# WIFI.net
KiCad netlist of a schematic drawn in Altium Designer
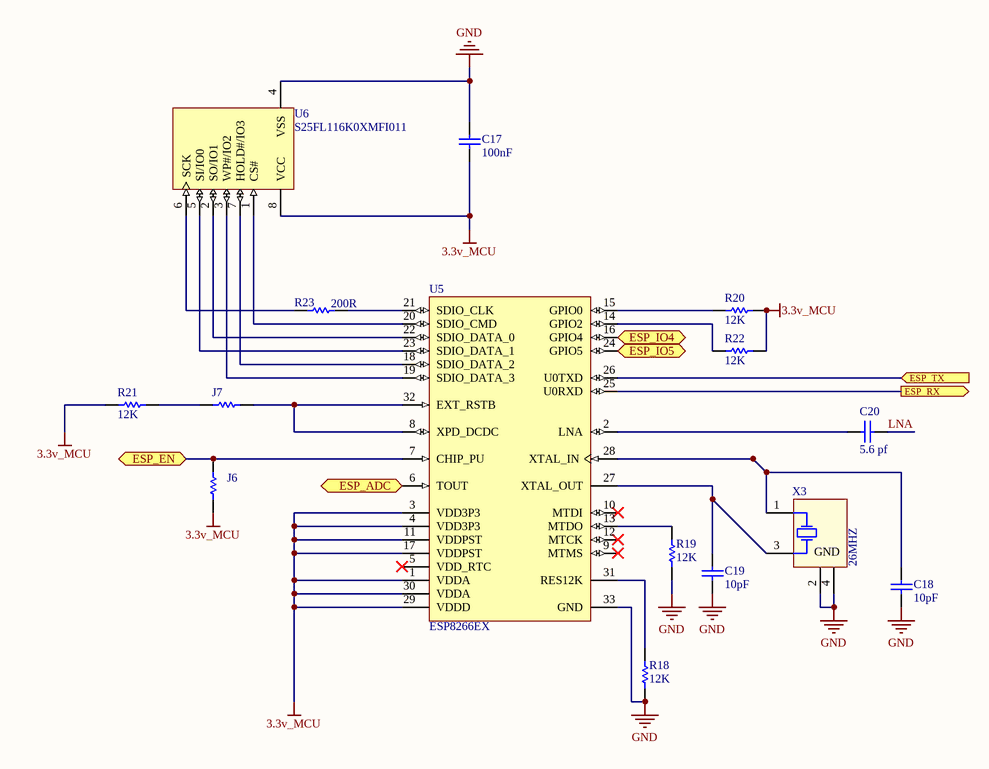
[diagram p0: WIFI.SchDoc]

(export (version "E")
  (design (tool "Eeschema 10.0.6"))
  (components
    (comp (ref "C17")
      (value "100nF")
      (footprint "CAPC0603(1608)100_L")
      (description "CAP 100nF 16V ±5% 0603 (1608 Metric) Thickness 1mm SMD")
      (fields (field (name "TOLERANCE") "Â±5%"))
      (libsource (lib "Altium Content Vault") (part "CAP"))
    )
    (comp (ref "C18")
      (value "10pF")
      (footprint "CAPC0603(1608)100_L")
      (description "CAP 10pF 16V ±1% 0603 (1608 Metric) Thickness 1mm SMD")
      (fields (field (name "TOLERANCE") "Â±1%"))
      (libsource (lib "Altium Content Vault") (part "CAP"))
    )
    (comp (ref "C19")
      (value "10pF")
      (footprint "CAPC0603(1608)100_L")
      (description "CAP 10pF 16V ±1% 0603 (1608 Metric) Thickness 1mm SMD")
      (fields (field (name "TOLERANCE") "Â±1%"))
      (libsource (lib "Altium Content Vault") (part "CAP"))
    )
    (comp (ref "C20")
      (value "5.6 pf")
      (footprint "CAPC0603(1608)100_L")
      (description "CAP 5.6pF 25V ±0.1pF 0603 (1608 Metric) Thickness 1mm SMD")
      (fields (field (name "TOLERANCE") "Â±0.1pF"))
      (libsource (lib "Altium Content Vault") (part "CAP"))
    )
    (comp (ref "J6")
      (value "~")
      (footprint "RESC1608X55X30LL10T20_A")
      (description "Chip Resistor, 0 Ohm, +/- 5%, 100 mW, -55 to 155 degC, 0603 (1608 Metric), RoHS, Tape and Reel")
      (fields (field (name "TOLERANCE") "Jumper") (field (name "MANUFACTURER") "Rohm"))
      (libsource (lib "Altium Content Vault") (part "RES-2"))
    )
    (comp (ref "J7")
      (value "~")
      (footprint "RESC1608X55X30LL10T20_A")
      (description "Chip Resistor, 0 Ohm, +/- 5%, 100 mW, -55 to 155 degC, 0603 (1608 Metric), RoHS, Tape and Reel")
      (fields (field (name "TOLERANCE") "Jumper") (field (name "MANUFACTURER") "Rohm"))
      (libsource (lib "Altium Content Vault") (part "RES-2"))
    )
    (comp (ref "R18")
      (value "12K")
      (footprint "RESC1609X55X30LL15T15")
      (description "Chip Resistor, 12 KOhm, +/- 1%, 0.1 W, -55 to 155 degC, 0603 (1608 Metric), RoHS, Tape and Reel")
      (fields (field (name "MANUFACTURER") "Panasonic") (field (name "TOLERANCE") "1%"))
      (libsource (lib "Altium Content Vault") (part "RES-2"))
    )
    (comp (ref "R19")
      (value "12K")
      (footprint "RESC1609X55X30LL15T15")
      (description "Chip Resistor, 12 KOhm, +/- 1%, 0.1 W, -55 to 155 degC, 0603 (1608 Metric), RoHS, Tape and Reel")
      (fields (field (name "MANUFACTURER") "Panasonic") (field (name "TOLERANCE") "1%"))
      (libsource (lib "Altium Content Vault") (part "RES-2"))
    )
    (comp (ref "R20")
      (value "12K")
      (footprint "RESC1609X55X30LL15T15")
      (description "Chip Resistor, 12 KOhm, +/- 1%, 0.1 W, -55 to 155 degC, 0603 (1608 Metric), RoHS, Tape and Reel")
      (fields (field (name "MANUFACTURER") "Panasonic") (field (name "TOLERANCE") "1%"))
      (libsource (lib "Altium Content Vault") (part "RES-2"))
    )
    (comp (ref "R21")
      (value "12K")
      (footprint "RESC1609X55X30LL15T15")
      (description "Chip Resistor, 12 KOhm, +/- 1%, 0.1 W, -55 to 155 degC, 0603 (1608 Metric), RoHS, Tape and Reel")
      (fields (field (name "MANUFACTURER") "Panasonic") (field (name "TOLERANCE") "1%"))
      (libsource (lib "Altium Content Vault") (part "RES-2"))
    )
    (comp (ref "R22")
      (value "12K")
      (footprint "RESC1609X55X30LL15T15")
      (description "Chip Resistor, 12 KOhm, +/- 1%, 0.1 W, -55 to 155 degC, 0603 (1608 Metric), RoHS, Tape and Reel")
      (fields (field (name "MANUFACTURER") "Panasonic") (field (name "TOLERANCE") "1%"))
      (libsource (lib "Altium Content Vault") (part "RES-2"))
    )
    (comp (ref "R23")
      (value "200R")
      (footprint "RESC0603(1608)_L")
      (description "200R 0.1W 1% 0603 (1608 Metric)  SMD")
      (fields (field (name "TOLERANCE") "1 %") (field (name "POWER") "0.1 W"))
      (libsource (lib "Altium Content Vault") (part "RES"))
    )
    (comp (ref "U5")
      (value "ESP8266EX")
      (footprint "ESFS-QFN-32_M")
      (description "Low-Power, Highly-Integrated Wi-Fi Solution, 2.5 to 3.6 V, 80 mA, -40 to 125 degC, 32-Pin QFN")
      (fields (field (name "MANUFACTURER") "Espressif Systems"))
      (libsource (lib "Altium Content Vault") (part "ESFS-ESP8266EX-32"))
    )
    (comp (ref "U6")
      (value "S25FL116K0XMFI011")
      (footprint "CYP-SOC-8_L")
      (description "SPI Flash Memory, 16 Mbit, 2.7 to 3.6 V, -40 to 85 degC, 8-Pin SOIC, RoHS, Tube")
      (fields (field (name "MANUFACTURER") "CypressSemiconductorCorp"))
      (libsource (lib "Altium Content Vault") (part "CYP-S25FL116K-SOIC-8"))
    )
    (comp (ref "X3")
      (value "26MHZ")
      (footprint "NDK-NX2016SA-26MHZ-EXS00A-CS06025-4_V")
      (description "Crystal, 26 MHz, 8 pF, for OA / AV / Short-range Wireless, -10 to 75 degC, 2.0 x 1.6 x 0.45 mm SMD")
      (fields (field (name "PARTNUMBER") "NX2016SA-26MHZ-EXS00A-CS06025") (field (name "MANUFACTURER") "NDK"))
      (libsource (lib "Altium Content Vault") (part "NDK-NX2016SA-26MHZ-EXS00A-CS06025-4"))
    )
  )
  (nets
    (net (code "1") (name "/ESP_ADC") (class "Default")
      (node (ref "U5") (pin "6") (pinfunction "TOUT_6") (pintype "input"))
    )
    (net (code "2") (name "/ESP_EN") (class "Default")
      (node (ref "J6") (pin "2") (pinfunction "2_2") (pintype "passive"))
      (node (ref "U5") (pin "7") (pinfunction "CHIP_PU_7") (pintype "input"))
    )
    (net (code "3") (name "/ESP_IO4") (class "Default")
      (node (ref "U5") (pin "16") (pinfunction "GPIO4_16") (pintype "bidirectional"))
    )
    (net (code "4") (name "/ESP_IO5") (class "Default")
      (node (ref "U5") (pin "24") (pinfunction "GPIO5_24") (pintype "bidirectional"))
    )
    (net (code "5") (name "/ESP_RX") (class "Default")
      (node (ref "U5") (pin "25") (pinfunction "U0RXD_25") (pintype "bidirectional"))
    )
    (net (code "6") (name "/ESP_TX") (class "Default")
      (node (ref "U5") (pin "26") (pinfunction "U0TXD_26") (pintype "bidirectional"))
    )
    (net (code "7") (name "/LNA") (class "Default")
      (node (ref "C20") (pin "2") (pinfunction "2_2") (pintype "passive"))
    )
    (net (code "8") (name "3.3v_MCU") (class "Default")
      (node (ref "C17") (pin "2") (pinfunction "2_2") (pintype "passive"))
      (node (ref "J6") (pin "1") (pinfunction "1_1") (pintype "passive"))
      (node (ref "R20") (pin "1") (pinfunction "1_1") (pintype "passive"))
      (node (ref "R21") (pin "2") (pinfunction "2_2") (pintype "passive"))
      (node (ref "R22") (pin "1") (pinfunction "1_1") (pintype "passive"))
      (node (ref "U5") (pin "1") (pinfunction "VDDA_1") (pintype "power_in"))
      (node (ref "U5") (pin "11") (pinfunction "VDDPST_11") (pintype "power_in"))
      (node (ref "U5") (pin "17") (pinfunction "VDDPST_17") (pintype "power_in"))
      (node (ref "U5") (pin "29") (pinfunction "VDDD_29") (pintype "power_in"))
      (node (ref "U5") (pin "3") (pinfunction "VDD3P3_3") (pintype "power_in"))
      (node (ref "U5") (pin "30") (pinfunction "VDDA_30") (pintype "power_in"))
      (node (ref "U5") (pin "4") (pinfunction "VDD3P3_4") (pintype "power_in"))
      (node (ref "U6") (pin "8") (pinfunction "VCC_8") (pintype "power_in"))
    )
    (net (code "9") (name "GND") (class "Default")
      (node (ref "C17") (pin "1") (pinfunction "1_1") (pintype "passive"))
      (node (ref "C18") (pin "1") (pinfunction "1_1") (pintype "passive"))
      (node (ref "C19") (pin "1") (pinfunction "1_1") (pintype "passive"))
      (node (ref "R18") (pin "1") (pinfunction "1_1") (pintype "passive"))
      (node (ref "R19") (pin "1") (pinfunction "1_1") (pintype "passive"))
      (node (ref "U5") (pin "33") (pinfunction "GND_33") (pintype "power_in"))
      (node (ref "U6") (pin "4") (pinfunction "VSS_4") (pintype "power_in"))
      (node (ref "X3") (pin "2") (pinfunction "GND_2") (pintype "power_in"))
      (node (ref "X3") (pin "4") (pinfunction "GND_4") (pintype "power_in"))
    )
    (net (code "10") (name "Net-(J7-Pad2)") (class "Default")
      (node (ref "J7") (pin "2") (pinfunction "2_2") (pintype "passive"))
      (node (ref "R21") (pin "1") (pinfunction "1_1") (pintype "passive"))
    )
    (net (code "11") (name "Net-(U5-EXT_RSTB)") (class "Default")
      (node (ref "J7") (pin "1") (pinfunction "1_1") (pintype "passive"))
      (node (ref "U5") (pin "32") (pinfunction "EXT_RSTB_32") (pintype "input"))
      (node (ref "U5") (pin "8") (pinfunction "XPD_DCDC_8") (pintype "bidirectional"))
    )
    (net (code "12") (name "Net-(U5-GPIO0)") (class "Default")
      (node (ref "R20") (pin "2") (pinfunction "2_2") (pintype "passive"))
      (node (ref "U5") (pin "15") (pinfunction "GPIO0_15") (pintype "bidirectional"))
    )
    (net (code "13") (name "Net-(U5-GPIO2)") (class "Default")
      (node (ref "R22") (pin "2") (pinfunction "2_2") (pintype "passive"))
      (node (ref "U5") (pin "14") (pinfunction "GPIO2_14") (pintype "bidirectional"))
    )
    (net (code "14") (name "Net-(U5-LNA)") (class "Default")
      (node (ref "C20") (pin "1") (pinfunction "1_1") (pintype "passive"))
      (node (ref "U5") (pin "2") (pinfunction "LNA_2") (pintype "bidirectional"))
    )
    (net (code "15") (name "Net-(U5-MTDO)") (class "Default")
      (node (ref "R19") (pin "2") (pinfunction "2_2") (pintype "passive"))
      (node (ref "U5") (pin "13") (pinfunction "MTDO_13") (pintype "bidirectional"))
    )
    (net (code "16") (name "Net-(U5-RES12K)") (class "Default")
      (node (ref "R18") (pin "2") (pinfunction "2_2") (pintype "passive"))
      (node (ref "U5") (pin "31") (pinfunction "RES12K_31") (pintype "passive"))
    )
    (net (code "17") (name "Net-(U5-SDIO_CLK)") (class "Default")
      (node (ref "R23") (pin "2") (pinfunction "2_2") (pintype "passive"))
      (node (ref "U5") (pin "21") (pinfunction "SDIO_CLK_21") (pintype "bidirectional"))
    )
    (net (code "18") (name "Net-(U5-SDIO_CMD)") (class "Default")
      (node (ref "U5") (pin "20") (pinfunction "SDIO_CMD_20") (pintype "bidirectional"))
      (node (ref "U6") (pin "1") (pinfunction "CS#_1") (pintype "input"))
    )
    (net (code "19") (name "Net-(U5-SDIO_DATA_0)") (class "Default")
      (node (ref "U5") (pin "22") (pinfunction "SDIO_DATA_0_22") (pintype "bidirectional"))
      (node (ref "U6") (pin "2") (pinfunction "SO/IO1_2") (pintype "bidirectional"))
    )
    (net (code "20") (name "Net-(U5-SDIO_DATA_1)") (class "Default")
      (node (ref "U5") (pin "23") (pinfunction "SDIO_DATA_1_23") (pintype "bidirectional"))
      (node (ref "U6") (pin "5") (pinfunction "SI/IO0_5") (pintype "bidirectional"))
    )
    (net (code "21") (name "Net-(U5-SDIO_DATA_2)") (class "Default")
      (node (ref "U5") (pin "18") (pinfunction "SDIO_DATA_2_18") (pintype "bidirectional"))
      (node (ref "U6") (pin "7") (pinfunction "HOLD#/IO3_7") (pintype "bidirectional"))
    )
    (net (code "22") (name "Net-(U5-SDIO_DATA_3)") (class "Default")
      (node (ref "U5") (pin "19") (pinfunction "SDIO_DATA_3_19") (pintype "bidirectional"))
      (node (ref "U6") (pin "3") (pinfunction "WP#/IO2_3") (pintype "bidirectional"))
    )
    (net (code "23") (name "Net-(U5-XTAL_IN)") (class "Default")
      (node (ref "C18") (pin "2") (pinfunction "2_2") (pintype "passive"))
      (node (ref "U5") (pin "28") (pinfunction "XTAL_IN_28") (pintype "input"))
      (node (ref "X3") (pin "1") (pinfunction "X1_1") (pintype "passive"))
    )
    (net (code "24") (name "Net-(U5-XTAL_OUT)") (class "Default")
      (node (ref "C19") (pin "2") (pinfunction "2_2") (pintype "passive"))
      (node (ref "U5") (pin "27") (pinfunction "XTAL_OUT_27") (pintype "passive"))
      (node (ref "X3") (pin "3") (pinfunction "X2_3") (pintype "passive"))
    )
    (net (code "25") (name "Net-(U6-SCK)") (class "Default")
      (node (ref "R23") (pin "1") (pinfunction "1_1") (pintype "passive"))
      (node (ref "U6") (pin "6") (pinfunction "SCK_6") (pintype "input"))
    )
    (net (code "26") (name "unconnected-(U5-MTCK-Pad12)") (class "Default")
      (node (ref "U5") (pin "12") (pinfunction "MTCK_12") (pintype "bidirectional+no_connect"))
    )
    (net (code "27") (name "unconnected-(U5-MTDI-Pad10)") (class "Default")
      (node (ref "U5") (pin "10") (pinfunction "MTDI_10") (pintype "bidirectional+no_connect"))
    )
    (net (code "28") (name "unconnected-(U5-MTMS-Pad9)") (class "Default")
      (node (ref "U5") (pin "9") (pinfunction "MTMS_9") (pintype "bidirectional+no_connect"))
    )
    (net (code "29") (name "unconnected-(U5-VDD_RTC-Pad5)") (class "Default")
      (node (ref "U5") (pin "5") (pinfunction "VDD_RTC_5") (pintype "power_in+no_connect"))
    )
  )
)
